# I2C-IOexpander_16bit.net
KiCad netlist of a schematic drawn in Altium Designer
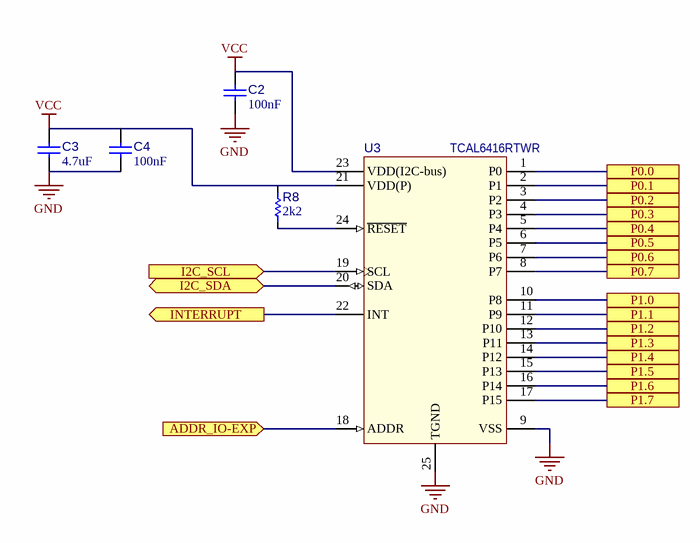
[diagram p0: I2C-IOexpander 16bit.SchDoc]

(export (version "E")
  (design (tool "Eeschema 10.0.6"))
  (components
    (comp (ref "C2")
      (value "100nF")
      (footprint "C_1005[0402]")
      (description "Capacitor type 1")
      (fields (field (name "TOLERANCE") "10%") (field (name "Comment") "Cap 100nF 0402"))
      (libsource (lib "TEP_243-Altium_DBLib") (part "capacitor"))
    )
    (comp (ref "C3")
      (value "4.7uF")
      (footprint "C_2012[0805]")
      (description "Capacitor type 1")
      (fields (field (name "TOLERANCE") "10%") (field (name "Comment") "Cap 4.7uF 0805"))
      (libsource (lib "TEP_243-Altium_DBLib") (part "capacitor"))
    )
    (comp (ref "C4")
      (value "100nF")
      (footprint "C_1005[0402]")
      (description "Capacitor type 1")
      (fields (field (name "TOLERANCE") "10%") (field (name "Comment") "Cap 100nF 0402"))
      (libsource (lib "TEP_243-Altium_DBLib") (part "capacitor"))
    )
    (comp (ref "R8")
      (value "2k2")
      (footprint "R_1005[0402]")
      (description "Resistor type 1")
      (fields (field (name "TOLERANCE") "1%") (field (name "Comment") "Res 2k2 1% 0402"))
      (libsource (lib "TEP_243-Altium_DBLib") (part "resistor"))
    )
    (comp (ref "U3")
      (value "TCAL6416RTWR")
      (footprint "U_QFN50P400X400X90-24L")
      (description "IC I/O EXPANDER 16BIT  QFN24")
      (libsource (lib "TEP-AltiumLib-ICs") (part "U_PCAL6416AHF"))
    )
  )
  (nets
    (net (code "1") (name "/ADDR_IO-EXP") (class "Default")
      (node (ref "U3") (pin "18") (pinfunction "ADDR_18") (pintype "input"))
    )
    (net (code "2") (name "/I2C_SCL") (class "Default")
      (node (ref "U3") (pin "19") (pinfunction "SCL_19") (pintype "input"))
    )
    (net (code "3") (name "/I2C_SDA") (class "Default")
      (node (ref "U3") (pin "20") (pinfunction "SDA_20") (pintype "bidirectional"))
    )
    (net (code "4") (name "/INTERRUPT") (class "Default")
      (node (ref "U3") (pin "22") (pinfunction "INT_22") (pintype "open_collector"))
    )
    (net (code "5") (name "/P0.0") (class "Default")
      (node (ref "U3") (pin "1") (pinfunction "P0_1") (pintype "passive"))
    )
    (net (code "6") (name "/P0.1") (class "Default")
      (node (ref "U3") (pin "2") (pinfunction "P1_2") (pintype "passive"))
    )
    (net (code "7") (name "/P0.2") (class "Default")
      (node (ref "U3") (pin "3") (pinfunction "P2_3") (pintype "passive"))
    )
    (net (code "8") (name "/P0.3") (class "Default")
      (node (ref "U3") (pin "4") (pinfunction "P3_4") (pintype "passive"))
    )
    (net (code "9") (name "/P0.4") (class "Default")
      (node (ref "U3") (pin "5") (pinfunction "P4_5") (pintype "passive"))
    )
    (net (code "10") (name "/P0.5") (class "Default")
      (node (ref "U3") (pin "6") (pinfunction "P5_6") (pintype "passive"))
    )
    (net (code "11") (name "/P0.6") (class "Default")
      (node (ref "U3") (pin "7") (pinfunction "P6_7") (pintype "passive"))
    )
    (net (code "12") (name "/P0.7") (class "Default")
      (node (ref "U3") (pin "8") (pinfunction "P7_8") (pintype "passive"))
    )
    (net (code "13") (name "/P1.0") (class "Default")
      (node (ref "U3") (pin "10") (pinfunction "P8_10") (pintype "passive"))
    )
    (net (code "14") (name "/P1.1") (class "Default")
      (node (ref "U3") (pin "11") (pinfunction "P9_11") (pintype "passive"))
    )
    (net (code "15") (name "/P1.2") (class "Default")
      (node (ref "U3") (pin "12") (pinfunction "P10_12") (pintype "passive"))
    )
    (net (code "16") (name "/P1.3") (class "Default")
      (node (ref "U3") (pin "13") (pinfunction "P11_13") (pintype "passive"))
    )
    (net (code "17") (name "/P1.4") (class "Default")
      (node (ref "U3") (pin "14") (pinfunction "P12_14") (pintype "passive"))
    )
    (net (code "18") (name "/P1.5") (class "Default")
      (node (ref "U3") (pin "15") (pinfunction "P13_15") (pintype "passive"))
    )
    (net (code "19") (name "/P1.6") (class "Default")
      (node (ref "U3") (pin "16") (pinfunction "P14_16") (pintype "passive"))
    )
    (net (code "20") (name "/P1.7") (class "Default")
      (node (ref "U3") (pin "17") (pinfunction "P15_17") (pintype "passive"))
    )
    (net (code "21") (name "GND") (class "Default")
      (node (ref "C2") (pin "1") (pinfunction "1_1") (pintype "passive"))
      (node (ref "C3") (pin "1") (pinfunction "1_1") (pintype "passive"))
      (node (ref "C4") (pin "1") (pinfunction "1_1") (pintype "passive"))
      (node (ref "U3") (pin "25") (pinfunction "TGND_25") (pintype "passive"))
      (node (ref "U3") (pin "9") (pinfunction "VSS_9") (pintype "power_in"))
    )
    (net (code "22") (name "Net-(U3-~{RESET})") (class "Default")
      (node (ref "R8") (pin "1") (pinfunction "1_1") (pintype "passive"))
      (node (ref "U3") (pin "24") (pinfunction "~{RESET}_24") (pintype "input"))
    )
    (net (code "23") (name "VCC") (class "Default")
      (node (ref "C2") (pin "2") (pinfunction "2_2") (pintype "passive"))
      (node (ref "C3") (pin "2") (pinfunction "2_2") (pintype "passive"))
      (node (ref "C4") (pin "2") (pinfunction "2_2") (pintype "passive"))
      (node (ref "R8") (pin "2") (pinfunction "2_2") (pintype "passive"))
      (node (ref "U3") (pin "21") (pinfunction "VDD(P)_21") (pintype "power_in"))
      (node (ref "U3") (pin "23") (pinfunction "VDD(I2C-bus)_23") (pintype "power_in"))
    )
  )
)
